# VisualightMicroBulb_02.net
KiCad netlist of a schematic drawn in EAGLE
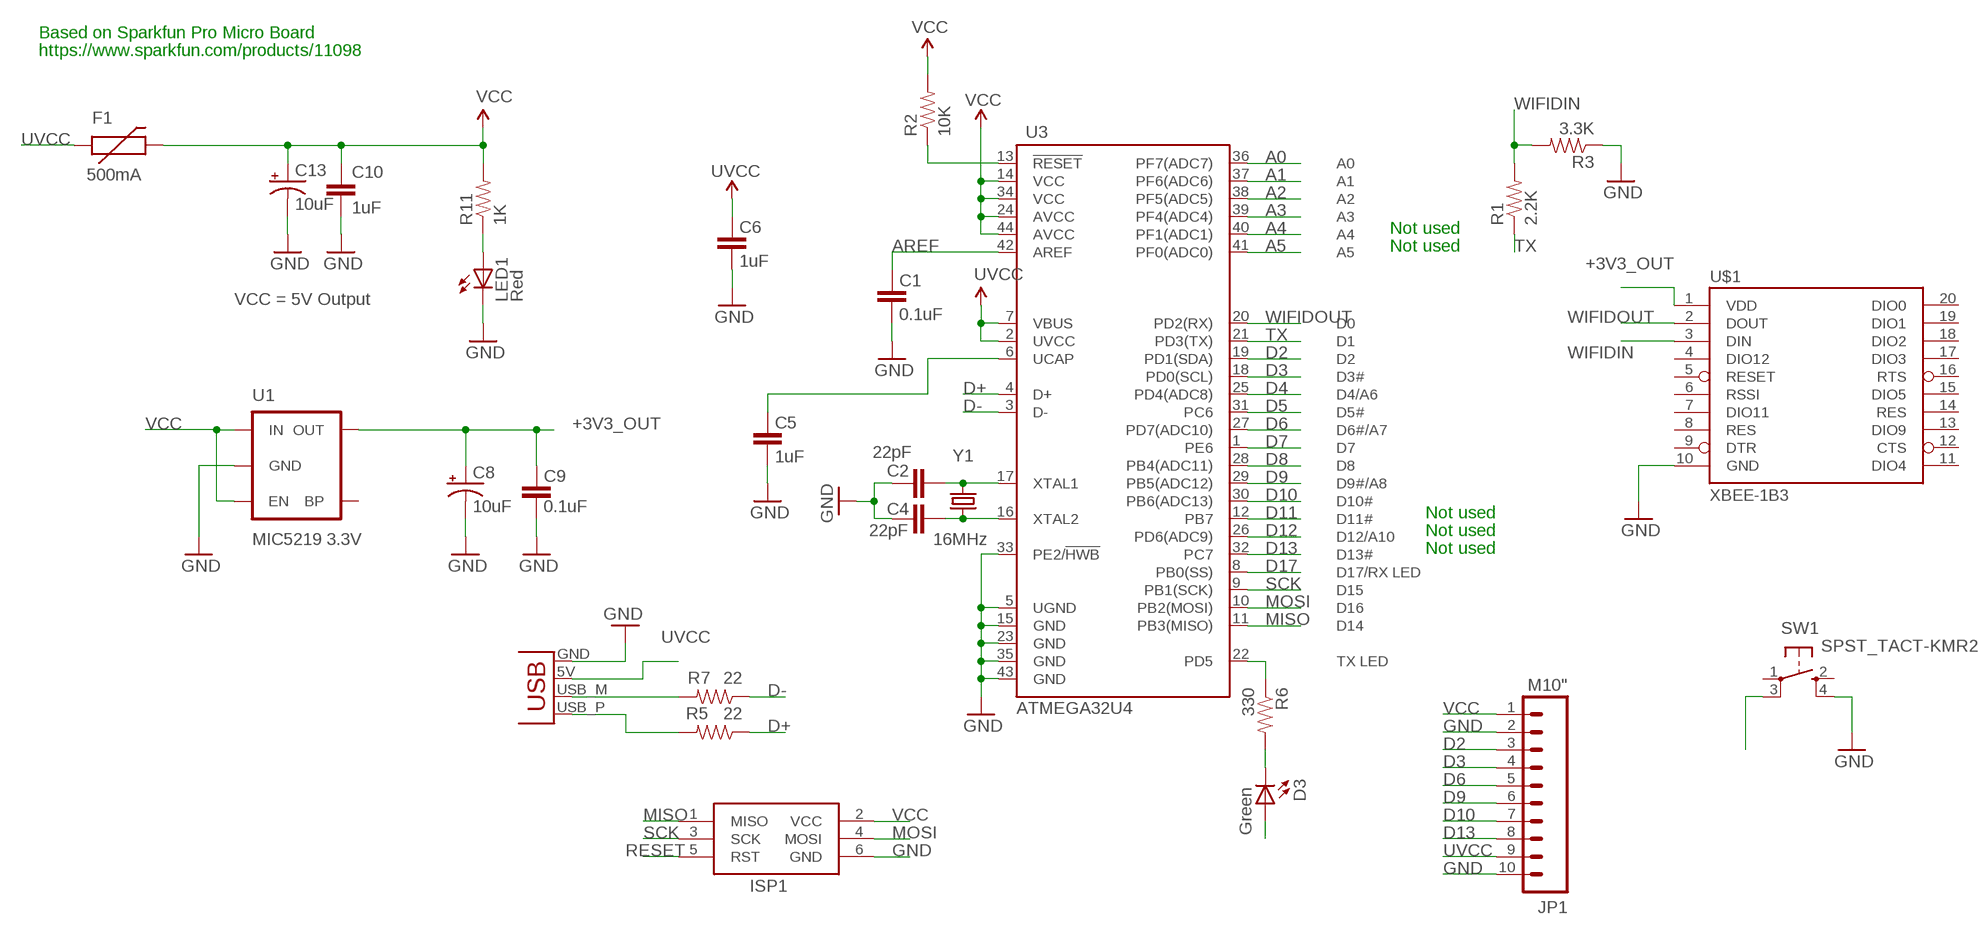
[diagram p0: schematic, sheet 1]

(export (version "E")
  (design (tool "Eeschema 10.0.6"))
  (components
    (comp (ref "C1")
      (value "0.1uF")
      (footprint "eagle-import:0402-CAP")
      (libsource (lib "eagle-import") (part "CAP0402-CAP"))
    )
    (comp (ref "C2")
      (value "22pF")
      (footprint "eagle-import:0402-CAP")
      (libsource (lib "eagle-import") (part "CAP0402-CAP"))
    )
    (comp (ref "C4")
      (value "22pF")
      (footprint "eagle-import:0402-CAP")
      (libsource (lib "eagle-import") (part "CAP0402-CAP"))
    )
    (comp (ref "C5")
      (value "1uF")
      (footprint "eagle-import:0402-CAP")
      (libsource (lib "eagle-import") (part "CAP0402-CAP"))
    )
    (comp (ref "C6")
      (value "1uF")
      (footprint "eagle-import:0402-CAP")
      (libsource (lib "eagle-import") (part "CAP0402-CAP"))
    )
    (comp (ref "C8")
      (value "10uF")
      (footprint "eagle-import:EIA3216")
      (libsource (lib "eagle-import") (part "CAP_POL1206"))
    )
    (comp (ref "C9")
      (value "0.1uF")
      (footprint "eagle-import:0402-CAP")
      (libsource (lib "eagle-import") (part "CAP0402-CAP"))
    )
    (comp (ref "C10")
      (value "1uF")
      (footprint "eagle-import:0402-CAP")
      (libsource (lib "eagle-import") (part "CAP0402-CAP"))
    )
    (comp (ref "C13")
      (value "10uF")
      (footprint "eagle-import:EIA3216")
      (libsource (lib "eagle-import") (part "CAP_POL1206"))
    )
    (comp (ref "D3")
      (value "Green")
      (footprint "eagle-import:LED-0603")
      (libsource (lib "eagle-import") (part "LED0603"))
    )
    (comp (ref "F1")
      (value "500mA")
      (footprint "eagle-import:PTC-1206")
      (libsource (lib "eagle-import") (part "PTCSMD"))
    )
    (comp (ref "ISP1")
      (value "AVRISP-6")
      (footprint "eagle-import:AVRISP")
      (libsource (lib "eagle-import") (part "AVRISP-6"))
    )
    (comp (ref "JP1")
      (value "M10\"")
      (footprint "eagle-import:1X10")
      (libsource (lib "eagle-import") (part "M10{dblquote}"))
    )
    (comp (ref "LED1")
      (value "Red")
      (footprint "eagle-import:LED-0603")
      (libsource (lib "eagle-import") (part "LED0603"))
    )
    (comp (ref "R1")
      (value "2.2K")
      (footprint "eagle-import:0402-RES")
      (libsource (lib "eagle-import") (part "RESISTOR0402-RES"))
    )
    (comp (ref "R2")
      (value "10K")
      (footprint "eagle-import:0402-RES")
      (libsource (lib "eagle-import") (part "RESISTOR0402-RES"))
    )
    (comp (ref "R3")
      (value "3.3K")
      (footprint "eagle-import:0402-RES")
      (libsource (lib "eagle-import") (part "RESISTOR0402-RES"))
    )
    (comp (ref "R5")
      (value "22")
      (footprint "eagle-import:0402-RES")
      (libsource (lib "eagle-import") (part "RESISTOR0402-RES"))
    )
    (comp (ref "R6")
      (value "330")
      (footprint "eagle-import:0402-RES")
      (libsource (lib "eagle-import") (part "RESISTOR0402-RES"))
    )
    (comp (ref "R7")
      (value "22")
      (footprint "eagle-import:0402-RES")
      (libsource (lib "eagle-import") (part "RESISTOR0402-RES"))
    )
    (comp (ref "R11")
      (value "1K")
      (footprint "eagle-import:0402-RES")
      (libsource (lib "eagle-import") (part "RESISTOR0402-RES"))
    )
    (comp (ref "SW1")
      (value "SPST_TACT-KMR2")
      (footprint "eagle-import:KMR2")
      (libsource (lib "eagle-import") (part "SPST_TACT-KMR2"))
    )
    (comp (ref "U$1")
      (value "XBEE-1B3")
      (footprint "eagle-import:XBEE-SMD")
      (libsource (lib "eagle-import") (part "XBEE-1B3"))
    )
    (comp (ref "U1")
      (value "MIC5219 3.3V")
      (footprint "eagle-import:SOT23-5")
      (libsource (lib "eagle-import") (part "V_REG_MIC52193.3V"))
    )
    (comp (ref "U3")
      (value "ATMEGA32U4")
      (footprint "eagle-import:SPARKFUN-DIGITALIC_TQFP44")
      (libsource (lib "eagle-import") (part "ATMEGA32U4TQFP"))
    )
    (comp (ref "X2")
      (value "USBPCB")
      (footprint "eagle-import:USB-A-PCB")
      (libsource (lib "eagle-import") (part "USBPCB"))
    )
    (comp (ref "Y1")
      (value "16MHz")
      (footprint "eagle-import:CRYSTAL-SMD-5X3")
      (libsource (lib "eagle-import") (part "CRYSTAL5X3"))
    )
  )
  (nets
    (net (code "1") (name "/+3V3_OUT") (class "Default")
      (node (ref "C8") (pin "A") (pinfunction "+_A") (pintype "passive"))
      (node (ref "C9") (pin "2") (pinfunction "2_2") (pintype "passive"))
      (node (ref "U$1") (pin "1") (pinfunction "VDD_1") (pintype "power_in"))
      (node (ref "U1") (pin "5") (pinfunction "OUT_5") (pintype "passive"))
    )
    (net (code "2") (name "/A0") (class "Default")
      (node (ref "U3") (pin "36") (pinfunction "PF7(ADC7)_36") (pintype "bidirectional"))
    )
    (net (code "3") (name "/A1") (class "Default")
      (node (ref "U3") (pin "37") (pinfunction "PF6(ADC6)_37") (pintype "bidirectional"))
    )
    (net (code "4") (name "/A2") (class "Default")
      (node (ref "U3") (pin "38") (pinfunction "PF5(ADC5)_38") (pintype "bidirectional"))
    )
    (net (code "5") (name "/A3") (class "Default")
      (node (ref "U3") (pin "39") (pinfunction "PF4(ADC4)_39") (pintype "bidirectional"))
    )
    (net (code "6") (name "/A4") (class "Default")
      (node (ref "U3") (pin "40") (pinfunction "PF1(ADC1)_40") (pintype "bidirectional"))
    )
    (net (code "7") (name "/A5") (class "Default")
      (node (ref "U3") (pin "41") (pinfunction "PF0(ADC0)_41") (pintype "bidirectional"))
    )
    (net (code "8") (name "/AREF") (class "Default")
      (node (ref "C1") (pin "2") (pinfunction "2_2") (pintype "passive"))
      (node (ref "U3") (pin "42") (pinfunction "AREF_42") (pintype "bidirectional"))
    )
    (net (code "9") (name "/D+") (class "Default")
      (node (ref "R5") (pin "1") (pinfunction "1_1") (pintype "passive"))
      (node (ref "U3") (pin "4") (pinfunction "D+_4") (pintype "bidirectional"))
    )
    (net (code "10") (name "/D-") (class "Default")
      (node (ref "R7") (pin "1") (pinfunction "1_1") (pintype "passive"))
      (node (ref "U3") (pin "3") (pinfunction "D-_3") (pintype "bidirectional"))
    )
    (net (code "11") (name "/D2") (class "Default")
      (node (ref "JP1") (pin "3") (pinfunction "3_3") (pintype "passive"))
      (node (ref "U3") (pin "19") (pinfunction "PD1(SDA)_19") (pintype "bidirectional"))
    )
    (net (code "12") (name "/D3") (class "Default")
      (node (ref "JP1") (pin "4") (pinfunction "4_4") (pintype "passive"))
      (node (ref "U3") (pin "18") (pinfunction "PD0(SCL)_18") (pintype "bidirectional"))
    )
    (net (code "13") (name "/D4") (class "Default")
      (node (ref "U3") (pin "25") (pinfunction "PD4(ADC8)_25") (pintype "bidirectional"))
    )
    (net (code "14") (name "/D5") (class "Default")
      (node (ref "U3") (pin "31") (pinfunction "PC6_31") (pintype "bidirectional"))
    )
    (net (code "15") (name "/D6") (class "Default")
      (node (ref "JP1") (pin "5") (pinfunction "5_5") (pintype "passive"))
      (node (ref "U3") (pin "27") (pinfunction "PD7(ADC10)_27") (pintype "bidirectional"))
    )
    (net (code "16") (name "/D7") (class "Default")
      (node (ref "SW1") (pin "3") (pinfunction "P1_3") (pintype "passive"))
      (node (ref "U3") (pin "1") (pinfunction "PE6_1") (pintype "bidirectional"))
    )
    (net (code "17") (name "/D8") (class "Default")
      (node (ref "U3") (pin "28") (pinfunction "PB4(ADC11)_28") (pintype "bidirectional"))
    )
    (net (code "18") (name "/D9") (class "Default")
      (node (ref "JP1") (pin "6") (pinfunction "6_6") (pintype "passive"))
      (node (ref "U3") (pin "29") (pinfunction "PB5(ADC12)_29") (pintype "bidirectional"))
    )
    (net (code "19") (name "/D10") (class "Default")
      (node (ref "JP1") (pin "7") (pinfunction "7_7") (pintype "passive"))
      (node (ref "U3") (pin "30") (pinfunction "PB6(ADC13)_30") (pintype "bidirectional"))
    )
    (net (code "20") (name "/D11") (class "Default")
      (node (ref "U3") (pin "12") (pinfunction "PB7_12") (pintype "bidirectional"))
    )
    (net (code "21") (name "/D12") (class "Default")
      (node (ref "U3") (pin "26") (pinfunction "PD6(ADC9)_26") (pintype "bidirectional"))
    )
    (net (code "22") (name "/D13") (class "Default")
      (node (ref "JP1") (pin "8") (pinfunction "8_8") (pintype "passive"))
      (node (ref "U3") (pin "32") (pinfunction "PC7_32") (pintype "bidirectional"))
    )
    (net (code "23") (name "/D17") (class "Default")
      (node (ref "U3") (pin "8") (pinfunction "PB0(SS)_8") (pintype "bidirectional"))
    )
    (net (code "24") (name "/MISO") (class "Default")
      (node (ref "ISP1") (pin "1") (pinfunction "MISO_1") (pintype "input"))
      (node (ref "U3") (pin "11") (pinfunction "PB3(MISO)_11") (pintype "bidirectional"))
    )
    (net (code "25") (name "/MOSI") (class "Default")
      (node (ref "ISP1") (pin "4") (pinfunction "MOSI_4") (pintype "output"))
      (node (ref "U3") (pin "10") (pinfunction "PB2(MOSI)_10") (pintype "bidirectional"))
    )
    (net (code "26") (name "/RESET") (class "Default")
      (node (ref "ISP1") (pin "5") (pinfunction "RST_5") (pintype "output"))
      (node (ref "R2") (pin "1") (pinfunction "1_1") (pintype "passive"))
      (node (ref "U3") (pin "13") (pinfunction "~{RESET}_13") (pintype "bidirectional"))
    )
    (net (code "27") (name "/SCK") (class "Default")
      (node (ref "ISP1") (pin "3") (pinfunction "SCK_3") (pintype "output"))
      (node (ref "U3") (pin "9") (pinfunction "PB1(SCK)_9") (pintype "bidirectional"))
    )
    (net (code "28") (name "/TX") (class "Default")
      (node (ref "R1") (pin "1") (pinfunction "1_1") (pintype "passive"))
      (node (ref "U3") (pin "21") (pinfunction "PD3(TX)_21") (pintype "bidirectional"))
    )
    (net (code "29") (name "/WIFIDIN") (class "Default")
      (node (ref "R1") (pin "2") (pinfunction "2_2") (pintype "passive"))
      (node (ref "R3") (pin "2") (pinfunction "2_2") (pintype "passive"))
      (node (ref "U$1") (pin "3") (pinfunction "DIN_3") (pintype "input"))
    )
    (net (code "30") (name "/WIFIDOUT") (class "Default")
      (node (ref "U$1") (pin "2") (pinfunction "DOUT_2") (pintype "output"))
      (node (ref "U3") (pin "20") (pinfunction "PD2(RX)_20") (pintype "bidirectional"))
    )
    (net (code "31") (name "GND") (class "Default")
      (node (ref "C1") (pin "1") (pinfunction "1_1") (pintype "passive"))
      (node (ref "C10") (pin "2") (pinfunction "2_2") (pintype "passive"))
      (node (ref "C13") (pin "C") (pinfunction "-_C") (pintype "passive"))
      (node (ref "C2") (pin "2") (pinfunction "2_2") (pintype "passive"))
      (node (ref "C4") (pin "2") (pinfunction "2_2") (pintype "passive"))
      (node (ref "C5") (pin "1") (pinfunction "1_1") (pintype "passive"))
      (node (ref "C6") (pin "1") (pinfunction "1_1") (pintype "passive"))
      (node (ref "C8") (pin "C") (pinfunction "-_C") (pintype "passive"))
      (node (ref "C9") (pin "1") (pinfunction "1_1") (pintype "passive"))
      (node (ref "ISP1") (pin "6") (pinfunction "GND_6") (pintype "power_in"))
      (node (ref "JP1") (pin "10") (pinfunction "10_10") (pintype "passive"))
      (node (ref "JP1") (pin "2") (pinfunction "2_2") (pintype "passive"))
      (node (ref "LED1") (pin "C") (pinfunction "C_C") (pintype "passive"))
      (node (ref "R3") (pin "1") (pinfunction "1_1") (pintype "passive"))
      (node (ref "SW1") (pin "4") (pinfunction "S1_4") (pintype "passive"))
      (node (ref "U$1") (pin "10") (pinfunction "GND_10") (pintype "power_in"))
      (node (ref "U1") (pin "2") (pinfunction "GND_2") (pintype "input"))
      (node (ref "U3") (pin "15") (pinfunction "GND_15") (pintype "bidirectional"))
      (node (ref "U3") (pin "23") (pinfunction "GND_23") (pintype "bidirectional"))
      (node (ref "U3") (pin "33") (pinfunction "PE2/~{HWB}_33") (pintype "bidirectional"))
      (node (ref "U3") (pin "35") (pinfunction "GND_35") (pintype "bidirectional"))
      (node (ref "U3") (pin "43") (pinfunction "GND_43") (pintype "bidirectional"))
      (node (ref "U3") (pin "5") (pinfunction "UGND_5") (pintype "bidirectional"))
      (node (ref "X2") (pin "GND") (pinfunction "GND_GND") (pintype "bidirectional"))
    )
    (net (code "32") (name "Net-(D3-PadC)") (class "Default")
      (node (ref "D3") (pin "C") (pinfunction "C_C") (pintype "passive"))
      (node (ref "R6") (pin "2") (pinfunction "2_2") (pintype "passive"))
    )
    (net (code "33") (name "Net-(LED1-PadA)") (class "Default")
      (node (ref "LED1") (pin "A") (pinfunction "A_A") (pintype "passive"))
      (node (ref "R11") (pin "1") (pinfunction "1_1") (pintype "passive"))
    )
    (net (code "34") (name "Net-(U3-PD5)") (class "Default")
      (node (ref "R6") (pin "1") (pinfunction "1_1") (pintype "passive"))
      (node (ref "U3") (pin "22") (pinfunction "PD5_22") (pintype "bidirectional"))
    )
    (net (code "35") (name "Net-(U3-UCAP)") (class "Default")
      (node (ref "C5") (pin "2") (pinfunction "2_2") (pintype "passive"))
      (node (ref "U3") (pin "6") (pinfunction "UCAP_6") (pintype "bidirectional"))
    )
    (net (code "36") (name "Net-(U3-XTAL1)") (class "Default")
      (node (ref "C2") (pin "1") (pinfunction "1_1") (pintype "passive"))
      (node (ref "U3") (pin "17") (pinfunction "XTAL1_17") (pintype "bidirectional"))
      (node (ref "Y1") (pin "3") (pinfunction "2_3") (pintype "passive"))
    )
    (net (code "37") (name "Net-(U3-XTAL2)") (class "Default")
      (node (ref "C4") (pin "1") (pinfunction "1_1") (pintype "passive"))
      (node (ref "U3") (pin "16") (pinfunction "XTAL2_16") (pintype "bidirectional"))
      (node (ref "Y1") (pin "1") (pinfunction "1_1") (pintype "passive"))
    )
    (net (code "38") (name "Net-(X2-D+)") (class "Default")
      (node (ref "R5") (pin "2") (pinfunction "2_2") (pintype "passive"))
      (node (ref "X2") (pin "USB_P") (pinfunction "D+_USB_P") (pintype "bidirectional"))
    )
    (net (code "39") (name "Net-(X2-D-)") (class "Default")
      (node (ref "R7") (pin "2") (pinfunction "2_2") (pintype "passive"))
      (node (ref "X2") (pin "USB_M") (pinfunction "D-_USB_M") (pintype "bidirectional"))
    )
    (net (code "40") (name "UVCC") (class "Default")
      (node (ref "C6") (pin "2") (pinfunction "2_2") (pintype "passive"))
      (node (ref "F1") (pin "1") (pinfunction "1_1") (pintype "bidirectional"))
      (node (ref "JP1") (pin "9") (pinfunction "9_9") (pintype "passive"))
      (node (ref "U3") (pin "2") (pinfunction "UVCC_2") (pintype "bidirectional"))
      (node (ref "U3") (pin "7") (pinfunction "VBUS_7") (pintype "bidirectional"))
      (node (ref "X2") (pin "5V") (pinfunction "VBUS_5V") (pintype "bidirectional"))
    )
    (net (code "41") (name "VCC") (class "Default")
      (node (ref "C10") (pin "1") (pinfunction "1_1") (pintype "passive"))
      (node (ref "C13") (pin "A") (pinfunction "+_A") (pintype "passive"))
      (node (ref "D3") (pin "A") (pinfunction "A_A") (pintype "passive"))
      (node (ref "F1") (pin "2") (pinfunction "2_2") (pintype "bidirectional"))
      (node (ref "ISP1") (pin "2") (pinfunction "VCC_2") (pintype "power_in"))
      (node (ref "JP1") (pin "1") (pinfunction "1_1") (pintype "passive"))
      (node (ref "R11") (pin "2") (pinfunction "2_2") (pintype "passive"))
      (node (ref "R2") (pin "2") (pinfunction "2_2") (pintype "passive"))
      (node (ref "U1") (pin "1") (pinfunction "IN_1") (pintype "input"))
      (node (ref "U1") (pin "3") (pinfunction "EN_3") (pintype "input"))
      (node (ref "U3") (pin "14") (pinfunction "VCC_14") (pintype "bidirectional"))
      (node (ref "U3") (pin "24") (pinfunction "AVCC_24") (pintype "bidirectional"))
      (node (ref "U3") (pin "34") (pinfunction "VCC_34") (pintype "bidirectional"))
      (node (ref "U3") (pin "44") (pinfunction "AVCC_44") (pintype "bidirectional"))
    )
    (net (code "42") (name "unconnected-(SW1-P-Pad1)") (class "Default")
      (node (ref "SW1") (pin "1") (pinfunction "P_1") (pintype "passive"))
    )
    (net (code "43") (name "unconnected-(SW1-S-Pad2)") (class "Default")
      (node (ref "SW1") (pin "2") (pinfunction "S_2") (pintype "passive"))
    )
    (net (code "44") (name "unconnected-(U$1-CTS-Pad12)") (class "Default")
      (node (ref "U$1") (pin "12") (pinfunction "CTS_12") (pintype "output"))
    )
    (net (code "45") (name "unconnected-(U$1-DIO0-Pad20)") (class "Default")
      (node (ref "U$1") (pin "20") (pinfunction "DIO0_20") (pintype "bidirectional"))
    )
    (net (code "46") (name "unconnected-(U$1-DIO1-Pad19)") (class "Default")
      (node (ref "U$1") (pin "19") (pinfunction "DIO1_19") (pintype "bidirectional"))
    )
    (net (code "47") (name "unconnected-(U$1-DIO2-Pad18)") (class "Default")
      (node (ref "U$1") (pin "18") (pinfunction "DIO2_18") (pintype "bidirectional"))
    )
    (net (code "48") (name "unconnected-(U$1-DIO3-Pad17)") (class "Default")
      (node (ref "U$1") (pin "17") (pinfunction "DIO3_17") (pintype "bidirectional"))
    )
    (net (code "49") (name "unconnected-(U$1-DIO4-Pad11)") (class "Default")
      (node (ref "U$1") (pin "11") (pinfunction "DIO4_11") (pintype "bidirectional"))
    )
    (net (code "50") (name "unconnected-(U$1-DIO5-Pad15)") (class "Default")
      (node (ref "U$1") (pin "15") (pinfunction "DIO5_15") (pintype "bidirectional"))
    )
    (net (code "51") (name "unconnected-(U$1-DIO9-Pad13)") (class "Default")
      (node (ref "U$1") (pin "13") (pinfunction "DIO9_13") (pintype "bidirectional"))
    )
    (net (code "52") (name "unconnected-(U$1-DIO11-Pad7)") (class "Default")
      (node (ref "U$1") (pin "7") (pinfunction "DIO11_7") (pintype "bidirectional"))
    )
    (net (code "53") (name "unconnected-(U$1-DIO12-Pad4)") (class "Default")
      (node (ref "U$1") (pin "4") (pinfunction "DIO12_4") (pintype "bidirectional"))
    )
    (net (code "54") (name "unconnected-(U$1-DTR-Pad9)") (class "Default")
      (node (ref "U$1") (pin "9") (pinfunction "DTR_9") (pintype "bidirectional"))
    )
    (net (code "55") (name "unconnected-(U$1-RES-Pad8)") (class "Default")
      (node (ref "U$1") (pin "8") (pinfunction "RES_8") (pintype "bidirectional"))
    )
    (net (code "56") (name "unconnected-(U$1-RES-Pad14)") (class "Default")
      (node (ref "U$1") (pin "14") (pinfunction "RES_14") (pintype "bidirectional"))
    )
    (net (code "57") (name "unconnected-(U$1-RESET-Pad5)") (class "Default")
      (node (ref "U$1") (pin "5") (pinfunction "RESET_5") (pintype "input"))
    )
    (net (code "58") (name "unconnected-(U$1-RSSI-Pad6)") (class "Default")
      (node (ref "U$1") (pin "6") (pinfunction "RSSI_6") (pintype "bidirectional"))
    )
    (net (code "59") (name "unconnected-(U$1-RTS-Pad16)") (class "Default")
      (node (ref "U$1") (pin "16") (pinfunction "RTS_16") (pintype "input"))
    )
    (net (code "60") (name "unconnected-(U1-BP-Pad4)") (class "Default")
      (node (ref "U1") (pin "4") (pinfunction "BP_4") (pintype "input"))
    )
  )
)
